# sous-vide.net
KiCad netlist of a schematic drawn in EAGLE
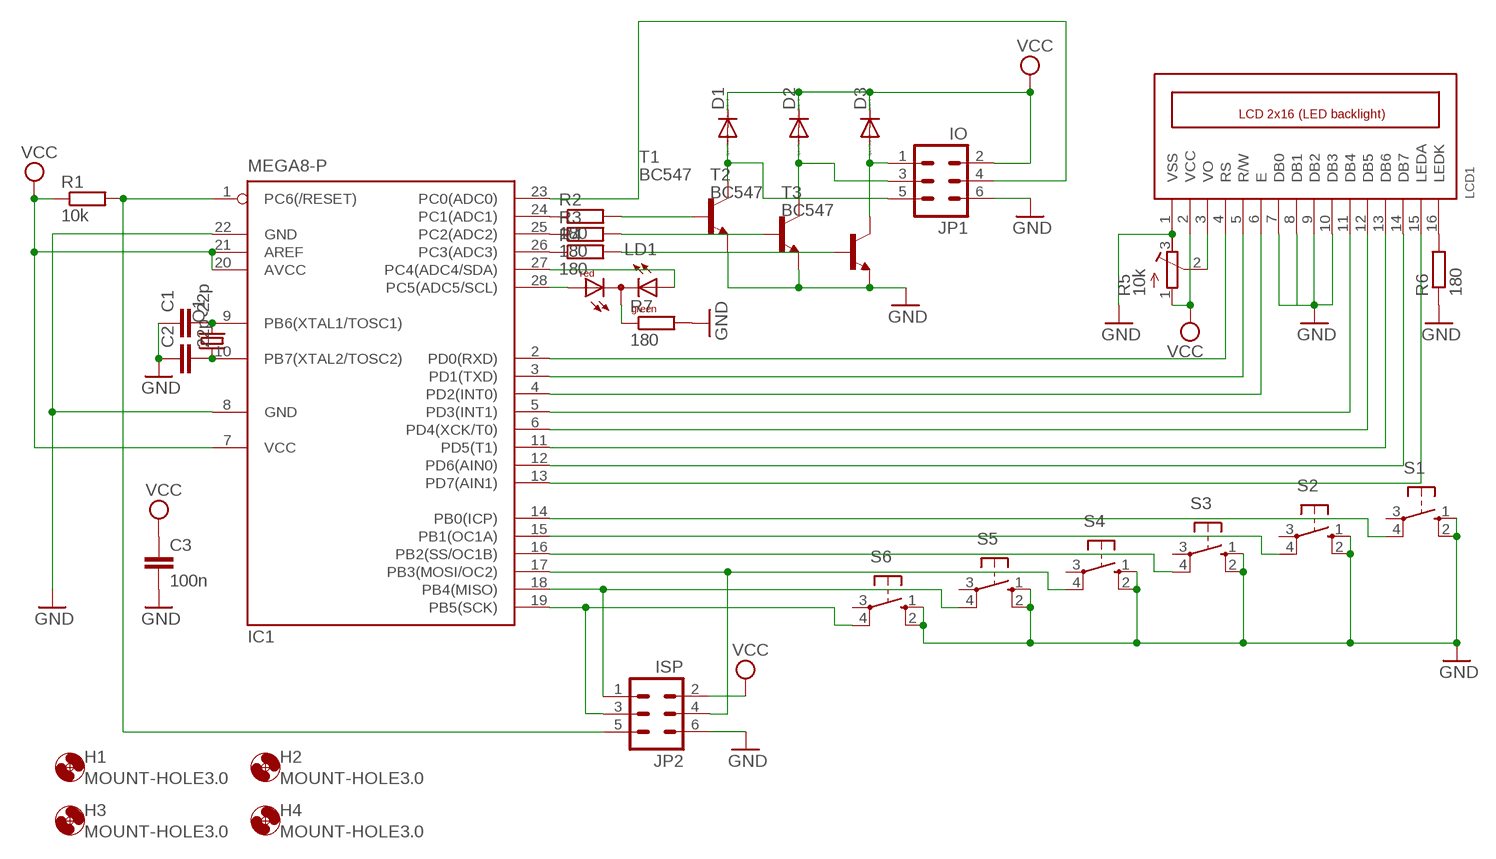
[diagram p0: schematic, sheet 1]

(export (version "E")
  (design (tool "Eeschema 10.0.6"))
  (components
    (comp (ref "C1")
      (value "22p")
      (footprint "eagle-import:C025-025X050")
      (libsource (lib "eagle-import") (part "C-EU025-025X050"))
    )
    (comp (ref "C2")
      (value "22p")
      (footprint "eagle-import:C025-025X050")
      (libsource (lib "eagle-import") (part "C-EU025-025X050"))
    )
    (comp (ref "C3")
      (value "100n")
      (footprint "eagle-import:C025-025X050")
      (libsource (lib "eagle-import") (part "C-EU025-025X050"))
    )
    (comp (ref "D1")
      (value "DIODE-D-2.5")
      (footprint "eagle-import:D-2.5")
      (libsource (lib "eagle-import") (part "DIODE-D-2.5"))
    )
    (comp (ref "D2")
      (value "DIODE-D-2.5")
      (footprint "eagle-import:D-2.5")
      (libsource (lib "eagle-import") (part "DIODE-D-2.5"))
    )
    (comp (ref "D3")
      (value "DIODE-D-2.5")
      (footprint "eagle-import:D-2.5")
      (libsource (lib "eagle-import") (part "DIODE-D-2.5"))
    )
    (comp (ref "H1")
      (value "MOUNT-HOLE3.0")
      (footprint "eagle-import:3,0")
      (libsource (lib "eagle-import") (part "MOUNT-HOLE3.0"))
    )
    (comp (ref "H2")
      (value "MOUNT-HOLE3.0")
      (footprint "eagle-import:3,0")
      (libsource (lib "eagle-import") (part "MOUNT-HOLE3.0"))
    )
    (comp (ref "H3")
      (value "MOUNT-HOLE3.0")
      (footprint "eagle-import:3,0")
      (libsource (lib "eagle-import") (part "MOUNT-HOLE3.0"))
    )
    (comp (ref "H4")
      (value "MOUNT-HOLE3.0")
      (footprint "eagle-import:3,0")
      (libsource (lib "eagle-import") (part "MOUNT-HOLE3.0"))
    )
    (comp (ref "IC1")
      (value "MEGA8-P")
      (footprint "eagle-import:DIL28-3")
      (libsource (lib "eagle-import") (part "MEGA8-P"))
    )
    (comp (ref "JP1")
      (value "IO")
      (footprint "eagle-import:ML6")
      (libsource (lib "eagle-import") (part "ML6"))
    )
    (comp (ref "JP2")
      (value "ISP")
      (footprint "eagle-import:ML6")
      (libsource (lib "eagle-import") (part "ML6"))
    )
    (comp (ref "LCD1")
      (value "LCD_2X16_SIL")
      (footprint "eagle-import:HY-1602F")
      (libsource (lib "eagle-import") (part "LCD_2X16_SIL"))
    )
    (comp (ref "LD1")
      (value "DUOLED-RG-C")
      (footprint "eagle-import:DUOLED-C-5MM")
      (libsource (lib "eagle-import") (part "DUOLED-RG-C"))
    )
    (comp (ref "Q1")
      (value "CRYSTALHC49U-V")
      (footprint "eagle-import:HC49U-V")
      (libsource (lib "eagle-import") (part "CRYSTALHC49U-V"))
    )
    (comp (ref "R1")
      (value "10k")
      (footprint "eagle-import:0207_7")
      (libsource (lib "eagle-import") (part "R-EU_0207/7"))
    )
    (comp (ref "R2")
      (value "180")
      (footprint "eagle-import:0207_2V")
      (libsource (lib "eagle-import") (part "R-EU_0207/2V"))
    )
    (comp (ref "R3")
      (value "180")
      (footprint "eagle-import:0207_2V")
      (libsource (lib "eagle-import") (part "R-EU_0207/2V"))
    )
    (comp (ref "R4")
      (value "180")
      (footprint "eagle-import:0207_2V")
      (libsource (lib "eagle-import") (part "R-EU_0207/2V"))
    )
    (comp (ref "R5")
      (value "10k")
      (footprint "eagle-import:RTRIM3339P")
      (libsource (lib "eagle-import") (part "R-TRIMM3339P"))
    )
    (comp (ref "R6")
      (value "180")
      (footprint "eagle-import:0207_7")
      (libsource (lib "eagle-import") (part "R-EU_0207/7"))
    )
    (comp (ref "R7")
      (value "180")
      (footprint "eagle-import:0207_7")
      (libsource (lib "eagle-import") (part "R-EU_0207/7"))
    )
    (comp (ref "S1")
      (value "40-XX")
      (footprint "eagle-import:B3F-40XX")
      (fields (field (name "MF") "OMRON COMPONENTS USA") (field (name "MPN") "B3F-4000"))
      (libsource (lib "eagle-import") (part "40-XX"))
    )
    (comp (ref "S2")
      (value "40-XX")
      (footprint "eagle-import:B3F-40XX")
      (fields (field (name "MF") "OMRON COMPONENTS USA") (field (name "MPN") "B3F-4000"))
      (libsource (lib "eagle-import") (part "40-XX"))
    )
    (comp (ref "S3")
      (value "40-XX")
      (footprint "eagle-import:B3F-40XX")
      (fields (field (name "MF") "OMRON COMPONENTS USA") (field (name "MPN") "B3F-4000"))
      (libsource (lib "eagle-import") (part "40-XX"))
    )
    (comp (ref "S4")
      (value "40-XX")
      (footprint "eagle-import:B3F-40XX")
      (fields (field (name "MF") "OMRON COMPONENTS USA") (field (name "MPN") "B3F-4000"))
      (libsource (lib "eagle-import") (part "40-XX"))
    )
    (comp (ref "S5")
      (value "40-XX")
      (footprint "eagle-import:B3F-40XX")
      (fields (field (name "MF") "OMRON COMPONENTS USA") (field (name "MPN") "B3F-4000"))
      (libsource (lib "eagle-import") (part "40-XX"))
    )
    (comp (ref "S6")
      (value "40-XX")
      (footprint "eagle-import:B3F-40XX")
      (fields (field (name "MF") "OMRON COMPONENTS USA") (field (name "MPN") "B3F-4000"))
      (libsource (lib "eagle-import") (part "40-XX"))
    )
    (comp (ref "T1")
      (value "BC547")
      (footprint "eagle-import:TO92")
      (libsource (lib "eagle-import") (part "BC547"))
    )
    (comp (ref "T2")
      (value "BC547")
      (footprint "eagle-import:TO92")
      (libsource (lib "eagle-import") (part "BC547"))
    )
    (comp (ref "T3")
      (value "BC547")
      (footprint "eagle-import:TO92")
      (libsource (lib "eagle-import") (part "BC547"))
    )
  )
  (nets
    (net (code "1") (name "GND") (class "Default")
      (node (ref "C1") (pin "1") (pinfunction "1_1") (pintype "passive"))
      (node (ref "C2") (pin "1") (pinfunction "1_1") (pintype "passive"))
      (node (ref "C3") (pin "2") (pinfunction "2_2") (pintype "passive"))
      (node (ref "IC1") (pin "22") (pinfunction "GND_22") (pintype "power_in"))
      (node (ref "IC1") (pin "8") (pinfunction "GND_8") (pintype "power_in"))
      (node (ref "JP1") (pin "6") (pinfunction "6_6") (pintype "passive"))
      (node (ref "JP2") (pin "6") (pinfunction "6_6") (pintype "passive"))
      (node (ref "LCD1") (pin "1") (pinfunction "VSS_1") (pintype "power_in"))
      (node (ref "LCD1") (pin "10") (pinfunction "DB3_10") (pintype "bidirectional"))
      (node (ref "LCD1") (pin "7") (pinfunction "DB0_7") (pintype "bidirectional"))
      (node (ref "LCD1") (pin "8") (pinfunction "DB1_8") (pintype "bidirectional"))
      (node (ref "LCD1") (pin "9") (pinfunction "DB2_9") (pintype "bidirectional"))
      (node (ref "R5") (pin "3") (pinfunction "A_3") (pintype "passive"))
      (node (ref "R6") (pin "1") (pinfunction "1_1") (pintype "passive"))
      (node (ref "R7") (pin "2") (pinfunction "2_2") (pintype "passive"))
      (node (ref "S1") (pin "1") (pinfunction "S_1") (pintype "passive"))
      (node (ref "S1") (pin "2") (pinfunction "S1_2") (pintype "passive"))
      (node (ref "S2") (pin "1") (pinfunction "S_1") (pintype "passive"))
      (node (ref "S2") (pin "2") (pinfunction "S1_2") (pintype "passive"))
      (node (ref "S3") (pin "1") (pinfunction "S_1") (pintype "passive"))
      (node (ref "S3") (pin "2") (pinfunction "S1_2") (pintype "passive"))
      (node (ref "S4") (pin "1") (pinfunction "S_1") (pintype "passive"))
      (node (ref "S4") (pin "2") (pinfunction "S1_2") (pintype "passive"))
      (node (ref "S5") (pin "1") (pinfunction "S_1") (pintype "passive"))
      (node (ref "S5") (pin "2") (pinfunction "S1_2") (pintype "passive"))
      (node (ref "S6") (pin "1") (pinfunction "S_1") (pintype "passive"))
      (node (ref "S6") (pin "2") (pinfunction "S1_2") (pintype "passive"))
      (node (ref "T1") (pin "1") (pinfunction "E_1") (pintype "passive"))
      (node (ref "T2") (pin "1") (pinfunction "E_1") (pintype "passive"))
      (node (ref "T3") (pin "1") (pinfunction "E_1") (pintype "passive"))
    )
    (net (code "2") (name "Net-(IC1-PB0(ICP))") (class "Default")
      (node (ref "IC1") (pin "14") (pinfunction "PB0(ICP)_14") (pintype "bidirectional"))
      (node (ref "S1") (pin "4") (pinfunction "P1_4") (pintype "passive"))
    )
    (net (code "3") (name "Net-(IC1-PB1(OC1A))") (class "Default")
      (node (ref "IC1") (pin "15") (pinfunction "PB1(OC1A)_15") (pintype "bidirectional"))
      (node (ref "S2") (pin "4") (pinfunction "P1_4") (pintype "passive"))
    )
    (net (code "4") (name "Net-(IC1-PB2(SS{slash}OC1B))") (class "Default")
      (node (ref "IC1") (pin "16") (pinfunction "PB2(SS/OC1B)_16") (pintype "bidirectional"))
      (node (ref "S3") (pin "4") (pinfunction "P1_4") (pintype "passive"))
    )
    (net (code "5") (name "Net-(IC1-PB3(MOSI{slash}OC2))") (class "Default")
      (node (ref "IC1") (pin "17") (pinfunction "PB3(MOSI/OC2)_17") (pintype "bidirectional"))
      (node (ref "JP2") (pin "4") (pinfunction "4_4") (pintype "passive"))
      (node (ref "S4") (pin "4") (pinfunction "P1_4") (pintype "passive"))
    )
    (net (code "6") (name "Net-(IC1-PB4(MISO))") (class "Default")
      (node (ref "IC1") (pin "18") (pinfunction "PB4(MISO)_18") (pintype "bidirectional"))
      (node (ref "JP2") (pin "1") (pinfunction "1_1") (pintype "passive"))
      (node (ref "S5") (pin "4") (pinfunction "P1_4") (pintype "passive"))
    )
    (net (code "7") (name "Net-(IC1-PB5(SCK))") (class "Default")
      (node (ref "IC1") (pin "19") (pinfunction "PB5(SCK)_19") (pintype "bidirectional"))
      (node (ref "JP2") (pin "3") (pinfunction "3_3") (pintype "passive"))
      (node (ref "S6") (pin "4") (pinfunction "P1_4") (pintype "passive"))
    )
    (net (code "8") (name "Net-(IC1-PB6(XTAL1{slash}TOSC1))") (class "Default")
      (node (ref "C1") (pin "2") (pinfunction "2_2") (pintype "passive"))
      (node (ref "IC1") (pin "9") (pinfunction "PB6(XTAL1/TOSC1)_9") (pintype "bidirectional"))
      (node (ref "Q1") (pin "2") (pinfunction "2_2") (pintype "passive"))
    )
    (net (code "9") (name "Net-(IC1-PB7(XTAL2{slash}TOSC2))") (class "Default")
      (node (ref "C2") (pin "2") (pinfunction "2_2") (pintype "passive"))
      (node (ref "IC1") (pin "10") (pinfunction "PB7(XTAL2/TOSC2)_10") (pintype "bidirectional"))
      (node (ref "Q1") (pin "1") (pinfunction "1_1") (pintype "passive"))
    )
    (net (code "10") (name "Net-(IC1-PC0(ADC0))") (class "Default")
      (node (ref "IC1") (pin "23") (pinfunction "PC0(ADC0)_23") (pintype "bidirectional"))
      (node (ref "JP1") (pin "4") (pinfunction "4_4") (pintype "passive"))
    )
    (net (code "11") (name "Net-(IC1-PC1(ADC1))") (class "Default")
      (node (ref "IC1") (pin "24") (pinfunction "PC1(ADC1)_24") (pintype "bidirectional"))
      (node (ref "R2") (pin "1") (pinfunction "1_1") (pintype "passive"))
    )
    (net (code "12") (name "Net-(IC1-PC2(ADC2))") (class "Default")
      (node (ref "IC1") (pin "25") (pinfunction "PC2(ADC2)_25") (pintype "bidirectional"))
      (node (ref "R3") (pin "1") (pinfunction "1_1") (pintype "passive"))
    )
    (net (code "13") (name "Net-(IC1-PC3(ADC3))") (class "Default")
      (node (ref "IC1") (pin "26") (pinfunction "PC3(ADC3)_26") (pintype "bidirectional"))
      (node (ref "R4") (pin "1") (pinfunction "1_1") (pintype "passive"))
    )
    (net (code "14") (name "Net-(IC1-PC4(ADC4{slash}SDA))") (class "Default")
      (node (ref "IC1") (pin "27") (pinfunction "PC4(ADC4/SDA)_27") (pintype "bidirectional"))
      (node (ref "LD1") (pin "AX") (pinfunction "AG_AX") (pintype "passive"))
    )
    (net (code "15") (name "Net-(IC1-PC5(ADC5{slash}SCL))") (class "Default")
      (node (ref "IC1") (pin "28") (pinfunction "PC5(ADC5/SCL)_28") (pintype "bidirectional"))
      (node (ref "LD1") (pin "AR") (pinfunction "AR_AR") (pintype "passive"))
    )
    (net (code "16") (name "Net-(IC1-PC6({slash}RESET))") (class "Default")
      (node (ref "IC1") (pin "1") (pinfunction "PC6(/RESET)_1") (pintype "bidirectional"))
      (node (ref "JP2") (pin "5") (pinfunction "5_5") (pintype "passive"))
      (node (ref "R1") (pin "2") (pinfunction "2_2") (pintype "passive"))
    )
    (net (code "17") (name "Net-(IC1-PD0(RXD))") (class "Default")
      (node (ref "IC1") (pin "2") (pinfunction "PD0(RXD)_2") (pintype "bidirectional"))
      (node (ref "LCD1") (pin "4") (pinfunction "RS_4") (pintype "input"))
    )
    (net (code "18") (name "Net-(IC1-PD1(TXD))") (class "Default")
      (node (ref "IC1") (pin "3") (pinfunction "PD1(TXD)_3") (pintype "bidirectional"))
      (node (ref "LCD1") (pin "5") (pinfunction "R/W_5") (pintype "input"))
    )
    (net (code "19") (name "Net-(IC1-PD2(INT0))") (class "Default")
      (node (ref "IC1") (pin "4") (pinfunction "PD2(INT0)_4") (pintype "bidirectional"))
      (node (ref "LCD1") (pin "6") (pinfunction "E_6") (pintype "input"))
    )
    (net (code "20") (name "Net-(IC1-PD3(INT1))") (class "Default")
      (node (ref "IC1") (pin "5") (pinfunction "PD3(INT1)_5") (pintype "bidirectional"))
      (node (ref "LCD1") (pin "11") (pinfunction "DB4_11") (pintype "bidirectional"))
    )
    (net (code "21") (name "Net-(IC1-PD4(XCK{slash}T0))") (class "Default")
      (node (ref "IC1") (pin "6") (pinfunction "PD4(XCK/T0)_6") (pintype "bidirectional"))
      (node (ref "LCD1") (pin "12") (pinfunction "DB5_12") (pintype "bidirectional"))
    )
    (net (code "22") (name "Net-(IC1-PD5(T1))") (class "Default")
      (node (ref "IC1") (pin "11") (pinfunction "PD5(T1)_11") (pintype "bidirectional"))
      (node (ref "LCD1") (pin "13") (pinfunction "DB6_13") (pintype "bidirectional"))
    )
    (net (code "23") (name "Net-(IC1-PD6(AIN0))") (class "Default")
      (node (ref "IC1") (pin "12") (pinfunction "PD6(AIN0)_12") (pintype "bidirectional"))
      (node (ref "LCD1") (pin "14") (pinfunction "DB7_14") (pintype "bidirectional"))
    )
    (net (code "24") (name "Net-(IC1-PD7(AIN1))") (class "Default")
      (node (ref "IC1") (pin "13") (pinfunction "PD7(AIN1)_13") (pintype "bidirectional"))
      (node (ref "LCD1") (pin "15") (pinfunction "LEDA_15") (pintype "passive"))
    )
    (net (code "25") (name "Net-(LCD1-LEDK)") (class "Default")
      (node (ref "LCD1") (pin "16") (pinfunction "LEDK_16") (pintype "passive"))
      (node (ref "R6") (pin "2") (pinfunction "2_2") (pintype "passive"))
    )
    (net (code "26") (name "Net-(LCD1-VO)") (class "Default")
      (node (ref "LCD1") (pin "3") (pinfunction "VO_3") (pintype "input"))
      (node (ref "R5") (pin "2") (pinfunction "S_2") (pintype "passive"))
    )
    (net (code "27") (name "Net-(LD1-PadC)") (class "Default")
      (node (ref "LD1") (pin "C") (pinfunction "C_C") (pintype "passive"))
      (node (ref "R7") (pin "1") (pinfunction "1_1") (pintype "passive"))
    )
    (net (code "28") (name "Net-(T1-B)") (class "Default")
      (node (ref "R2") (pin "2") (pinfunction "2_2") (pintype "passive"))
      (node (ref "T1") (pin "2") (pinfunction "B_2") (pintype "passive"))
    )
    (net (code "29") (name "Net-(T1-C)") (class "Default")
      (node (ref "D1") (pin "A") (pinfunction "A_A") (pintype "passive"))
      (node (ref "JP1") (pin "5") (pinfunction "5_5") (pintype "passive"))
      (node (ref "T1") (pin "3") (pinfunction "C_3") (pintype "passive"))
    )
    (net (code "30") (name "Net-(T2-B)") (class "Default")
      (node (ref "R3") (pin "2") (pinfunction "2_2") (pintype "passive"))
      (node (ref "T2") (pin "2") (pinfunction "B_2") (pintype "passive"))
    )
    (net (code "31") (name "Net-(T2-C)") (class "Default")
      (node (ref "D2") (pin "A") (pinfunction "A_A") (pintype "passive"))
      (node (ref "JP1") (pin "3") (pinfunction "3_3") (pintype "passive"))
      (node (ref "T2") (pin "3") (pinfunction "C_3") (pintype "passive"))
    )
    (net (code "32") (name "Net-(T3-B)") (class "Default")
      (node (ref "R4") (pin "2") (pinfunction "2_2") (pintype "passive"))
      (node (ref "T3") (pin "2") (pinfunction "B_2") (pintype "passive"))
    )
    (net (code "33") (name "Net-(T3-C)") (class "Default")
      (node (ref "D3") (pin "A") (pinfunction "A_A") (pintype "passive"))
      (node (ref "JP1") (pin "1") (pinfunction "1_1") (pintype "passive"))
      (node (ref "T3") (pin "3") (pinfunction "C_3") (pintype "passive"))
    )
    (net (code "34") (name "VCC") (class "Default")
      (node (ref "C3") (pin "1") (pinfunction "1_1") (pintype "passive"))
      (node (ref "D1") (pin "C") (pinfunction "C_C") (pintype "passive"))
      (node (ref "D2") (pin "C") (pinfunction "C_C") (pintype "passive"))
      (node (ref "D3") (pin "C") (pinfunction "C_C") (pintype "passive"))
      (node (ref "IC1") (pin "20") (pinfunction "AVCC_20") (pintype "power_in"))
      (node (ref "IC1") (pin "21") (pinfunction "AREF_21") (pintype "passive"))
      (node (ref "IC1") (pin "7") (pinfunction "VCC_7") (pintype "power_in"))
      (node (ref "JP1") (pin "2") (pinfunction "2_2") (pintype "passive"))
      (node (ref "JP2") (pin "2") (pinfunction "2_2") (pintype "passive"))
      (node (ref "LCD1") (pin "2") (pinfunction "VCC_2") (pintype "power_in"))
      (node (ref "R1") (pin "1") (pinfunction "1_1") (pintype "passive"))
      (node (ref "R5") (pin "1") (pinfunction "E_1") (pintype "passive"))
    )
    (net (code "35") (name "unconnected-(S1-P-Pad3)") (class "Default")
      (node (ref "S1") (pin "3") (pinfunction "P_3") (pintype "passive"))
    )
    (net (code "36") (name "unconnected-(S2-P-Pad3)") (class "Default")
      (node (ref "S2") (pin "3") (pinfunction "P_3") (pintype "passive"))
    )
    (net (code "37") (name "unconnected-(S3-P-Pad3)") (class "Default")
      (node (ref "S3") (pin "3") (pinfunction "P_3") (pintype "passive"))
    )
    (net (code "38") (name "unconnected-(S4-P-Pad3)") (class "Default")
      (node (ref "S4") (pin "3") (pinfunction "P_3") (pintype "passive"))
    )
    (net (code "39") (name "unconnected-(S5-P-Pad3)") (class "Default")
      (node (ref "S5") (pin "3") (pinfunction "P_3") (pintype "passive"))
    )
    (net (code "40") (name "unconnected-(S6-P-Pad3)") (class "Default")
      (node (ref "S6") (pin "3") (pinfunction "P_3") (pintype "passive"))
    )
  )
)
